# 2.net
KiCad netlist of a schematic drawn in EAGLE
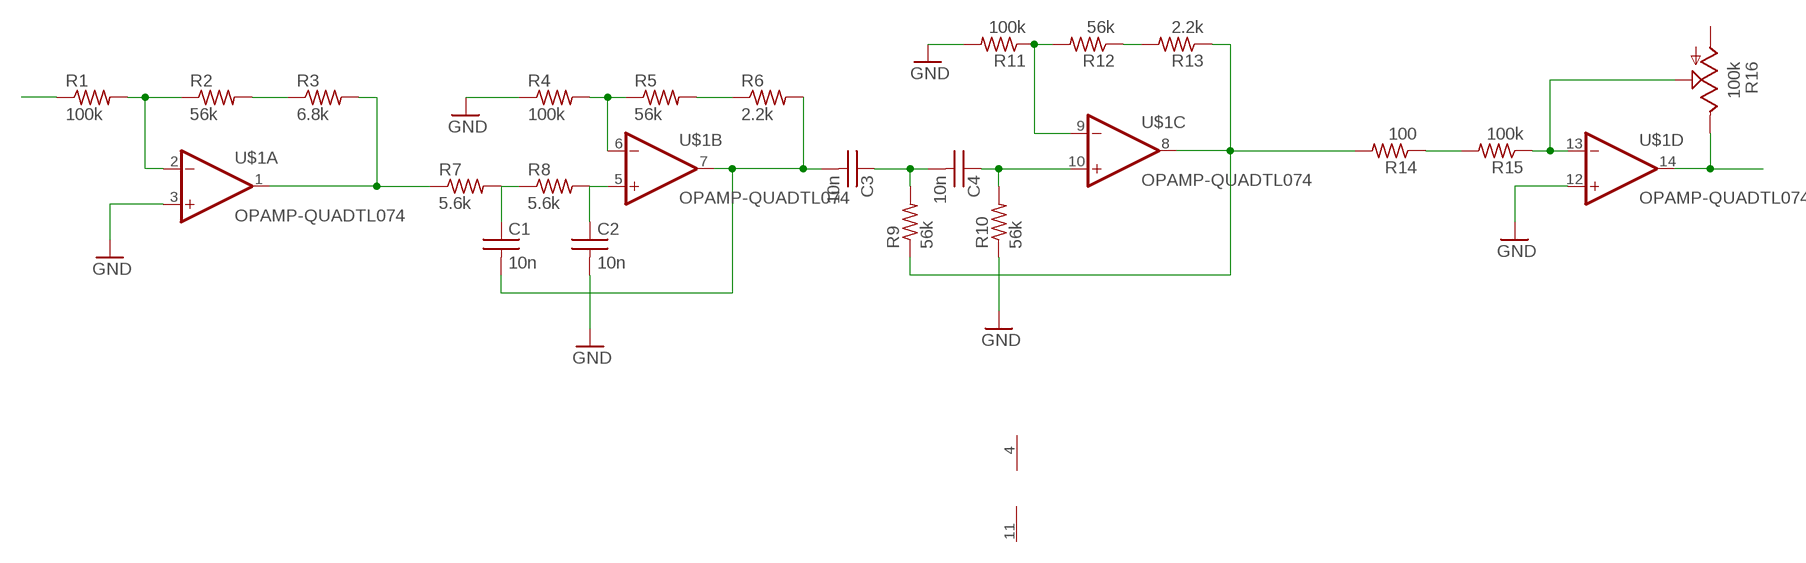
[diagram p0: schematic, sheet 1]

(export (version "E")
  (design (tool "Eeschema 10.0.6"))
  (components
    (comp (ref "C1")
      (value "10n")
      (footprint "eagle-import:BOX-2.5MM-7.2MM")
      (libsource (lib "eagle-import") (part "CAPACITOR"))
    )
    (comp (ref "C2")
      (value "10n")
      (footprint "eagle-import:BOX-2.5MM-7.2MM")
      (libsource (lib "eagle-import") (part "CAPACITOR"))
    )
    (comp (ref "C3")
      (value "10n")
      (footprint "eagle-import:BOX-2.5MM-7.2MM")
      (libsource (lib "eagle-import") (part "CAPACITOR"))
    )
    (comp (ref "C4")
      (value "10n")
      (footprint "eagle-import:BOX-2.5MM-7.2MM")
      (libsource (lib "eagle-import") (part "CAPACITOR"))
    )
    (comp (ref "R1")
      (value "100k")
      (footprint "eagle-import:0.25W-0.4IN-CARBONFILM")
      (libsource (lib "eagle-import") (part "RESISTOR0.25W-0.4IN-CARBONFILM"))
    )
    (comp (ref "R2")
      (value "56k")
      (footprint "eagle-import:0.25W-0.4IN-CARBONFILM")
      (libsource (lib "eagle-import") (part "RESISTOR0.25W-0.4IN-CARBONFILM"))
    )
    (comp (ref "R3")
      (value "6.8k")
      (footprint "eagle-import:0.25W-0.4IN-CARBONFILM")
      (libsource (lib "eagle-import") (part "RESISTOR0.25W-0.4IN-CARBONFILM"))
    )
    (comp (ref "R4")
      (value "100k")
      (footprint "eagle-import:0.25W-0.4IN-CARBONFILM")
      (libsource (lib "eagle-import") (part "RESISTOR0.25W-0.4IN-CARBONFILM"))
    )
    (comp (ref "R5")
      (value "56k")
      (footprint "eagle-import:0.25W-0.4IN-CARBONFILM")
      (libsource (lib "eagle-import") (part "RESISTOR0.25W-0.4IN-CARBONFILM"))
    )
    (comp (ref "R6")
      (value "2.2k")
      (footprint "eagle-import:0.25W-0.4IN-CARBONFILM")
      (libsource (lib "eagle-import") (part "RESISTOR0.25W-0.4IN-CARBONFILM"))
    )
    (comp (ref "R7")
      (value "5.6k")
      (footprint "eagle-import:0.25W-0.4IN-CARBONFILM")
      (libsource (lib "eagle-import") (part "RESISTOR0.25W-0.4IN-CARBONFILM"))
    )
    (comp (ref "R8")
      (value "5.6k")
      (footprint "eagle-import:0.25W-0.4IN-CARBONFILM")
      (libsource (lib "eagle-import") (part "RESISTOR0.25W-0.4IN-CARBONFILM"))
    )
    (comp (ref "R9")
      (value "56k")
      (footprint "eagle-import:0.25W-0.4IN-CARBONFILM")
      (libsource (lib "eagle-import") (part "RESISTOR0.25W-0.4IN-CARBONFILM"))
    )
    (comp (ref "R10")
      (value "56k")
      (footprint "eagle-import:0.25W-0.4IN-CARBONFILM")
      (libsource (lib "eagle-import") (part "RESISTOR0.25W-0.4IN-CARBONFILM"))
    )
    (comp (ref "R11")
      (value "100k")
      (footprint "eagle-import:0.25W-0.4IN-CARBONFILM")
      (libsource (lib "eagle-import") (part "RESISTOR0.25W-0.4IN-CARBONFILM"))
    )
    (comp (ref "R12")
      (value "56k")
      (footprint "eagle-import:0.25W-0.4IN-CARBONFILM")
      (libsource (lib "eagle-import") (part "RESISTOR0.25W-0.4IN-CARBONFILM"))
    )
    (comp (ref "R13")
      (value "2.2k")
      (footprint "eagle-import:0.25W-0.4IN-CARBONFILM")
      (libsource (lib "eagle-import") (part "RESISTOR0.25W-0.4IN-CARBONFILM"))
    )
    (comp (ref "R14")
      (value "100")
      (footprint "eagle-import:0.25W-0.4IN-CARBONFILM")
      (libsource (lib "eagle-import") (part "RESISTOR0.25W-0.4IN-CARBONFILM"))
    )
    (comp (ref "R15")
      (value "100k")
      (footprint "eagle-import:0.25W-0.4IN-CARBONFILM")
      (libsource (lib "eagle-import") (part "RESISTOR0.25W-0.4IN-CARBONFILM"))
    )
    (comp (ref "R16")
      (value "100k")
      (footprint "eagle-import:POT-SIDE-16MM-BITECH-P160KN")
      (libsource (lib "eagle-import") (part "POTENTIOMETERHORIZONTAL"))
    )
    (comp (ref "U$1")
      (value "OPAMP-QUADTL074")
      (footprint "eagle-import:DIP14")
      (libsource (lib "eagle-import") (part "OPAMP-QUADTL074"))
    )
  )
  (nets
    (net (code "1") (name "/VCC") (class "Default")
      (node (ref "U$1") (pin "4") (pinfunction "VCC_4") (pintype "power_in"))
    )
    (net (code "2") (name "/VEE") (class "Default")
      (node (ref "U$1") (pin "11") (pinfunction "VEE_11") (pintype "power_in"))
    )
    (net (code "3") (name "0") (class "Default")
      (node (ref "C2") (pin "P$2") (pinfunction "2_P$2") (pintype "passive"))
      (node (ref "R10") (pin "1") (pinfunction "1_1") (pintype "passive"))
      (node (ref "R11") (pin "2") (pinfunction "2_2") (pintype "passive"))
      (node (ref "R4") (pin "1") (pinfunction "1_1") (pintype "passive"))
      (node (ref "U$1") (pin "12") (pinfunction "IN+_12") (pintype "input"))
      (node (ref "U$1") (pin "3") (pinfunction "IN+_3") (pintype "input"))
    )
    (net (code "4") (name "Net-(C1-1)") (class "Default")
      (node (ref "C1") (pin "P$1") (pinfunction "1_P$1") (pintype "passive"))
      (node (ref "R7") (pin "2") (pinfunction "2_2") (pintype "passive"))
      (node (ref "R8") (pin "1") (pinfunction "1_1") (pintype "passive"))
    )
    (net (code "5") (name "Net-(C1-2)") (class "Default")
      (node (ref "C1") (pin "P$2") (pinfunction "2_P$2") (pintype "passive"))
      (node (ref "C3") (pin "P$2") (pinfunction "2_P$2") (pintype "passive"))
      (node (ref "R6") (pin "2") (pinfunction "2_2") (pintype "passive"))
      (node (ref "U$1") (pin "7") (pinfunction "OUT_7") (pintype "output"))
    )
    (net (code "6") (name "Net-(C2-1)") (class "Default")
      (node (ref "C2") (pin "P$1") (pinfunction "1_P$1") (pintype "passive"))
      (node (ref "R8") (pin "2") (pinfunction "2_2") (pintype "passive"))
      (node (ref "U$1") (pin "5") (pinfunction "IN+_5") (pintype "input"))
    )
    (net (code "7") (name "Net-(C3-1)") (class "Default")
      (node (ref "C3") (pin "P$1") (pinfunction "1_P$1") (pintype "passive"))
      (node (ref "C4") (pin "P$2") (pinfunction "2_P$2") (pintype "passive"))
      (node (ref "R9") (pin "2") (pinfunction "2_2") (pintype "passive"))
    )
    (net (code "8") (name "Net-(C4-1)") (class "Default")
      (node (ref "C4") (pin "P$1") (pinfunction "1_P$1") (pintype "passive"))
      (node (ref "R10") (pin "2") (pinfunction "2_2") (pintype "passive"))
      (node (ref "U$1") (pin "10") (pinfunction "IN+_10") (pintype "input"))
    )
    (net (code "9") (name "Net-(R2-Pad2)") (class "Default")
      (node (ref "R2") (pin "2") (pinfunction "2_2") (pintype "passive"))
      (node (ref "R3") (pin "1") (pinfunction "1_1") (pintype "passive"))
    )
    (net (code "10") (name "Net-(R5-Pad2)") (class "Default")
      (node (ref "R5") (pin "2") (pinfunction "2_2") (pintype "passive"))
      (node (ref "R6") (pin "1") (pinfunction "1_1") (pintype "passive"))
    )
    (net (code "11") (name "Net-(R12-Pad1)") (class "Default")
      (node (ref "R12") (pin "1") (pinfunction "1_1") (pintype "passive"))
      (node (ref "R13") (pin "2") (pinfunction "2_2") (pintype "passive"))
    )
    (net (code "12") (name "Net-(R14-Pad1)") (class "Default")
      (node (ref "R14") (pin "1") (pinfunction "1_1") (pintype "passive"))
      (node (ref "R15") (pin "2") (pinfunction "2_2") (pintype "passive"))
    )
    (net (code "13") (name "Net-(R16-2)") (class "Default")
      (node (ref "R15") (pin "1") (pinfunction "1_1") (pintype "passive"))
      (node (ref "R16") (pin "P$2") (pinfunction "2_P$2") (pintype "passive"))
      (node (ref "U$1") (pin "13") (pinfunction "IN-_13") (pintype "input"))
    )
    (net (code "14") (name "Net-(R16-3)") (class "Default")
      (node (ref "R16") (pin "P$3") (pinfunction "3_P$3") (pintype "passive"))
      (node (ref "U$1") (pin "14") (pinfunction "OUT_14") (pintype "output"))
    )
    (net (code "15") (name "Net-(U$1A-IN-)") (class "Default")
      (node (ref "R1") (pin "2") (pinfunction "2_2") (pintype "passive"))
      (node (ref "R2") (pin "1") (pinfunction "1_1") (pintype "passive"))
      (node (ref "U$1") (pin "2") (pinfunction "IN-_2") (pintype "input"))
    )
    (net (code "16") (name "Net-(U$1A-OUT)") (class "Default")
      (node (ref "R3") (pin "2") (pinfunction "2_2") (pintype "passive"))
      (node (ref "R7") (pin "1") (pinfunction "1_1") (pintype "passive"))
      (node (ref "U$1") (pin "1") (pinfunction "OUT_1") (pintype "output"))
    )
    (net (code "17") (name "Net-(U$1B-IN-)") (class "Default")
      (node (ref "R4") (pin "2") (pinfunction "2_2") (pintype "passive"))
      (node (ref "R5") (pin "1") (pinfunction "1_1") (pintype "passive"))
      (node (ref "U$1") (pin "6") (pinfunction "IN-_6") (pintype "input"))
    )
    (net (code "18") (name "Net-(U$1C-IN-)") (class "Default")
      (node (ref "R11") (pin "1") (pinfunction "1_1") (pintype "passive"))
      (node (ref "R12") (pin "2") (pinfunction "2_2") (pintype "passive"))
      (node (ref "U$1") (pin "9") (pinfunction "IN-_9") (pintype "input"))
    )
    (net (code "19") (name "Net-(U$1C-OUT)") (class "Default")
      (node (ref "R13") (pin "1") (pinfunction "1_1") (pintype "passive"))
      (node (ref "R14") (pin "2") (pinfunction "2_2") (pintype "passive"))
      (node (ref "R9") (pin "1") (pinfunction "1_1") (pintype "passive"))
      (node (ref "U$1") (pin "8") (pinfunction "OUT_8") (pintype "output"))
    )
    (net (code "20") (name "unconnected-(R1-Pad1)") (class "Default")
      (node (ref "R1") (pin "1") (pinfunction "1_1") (pintype "passive"))
    )
    (net (code "21") (name "unconnected-(R16-1-PadP$1)") (class "Default")
      (node (ref "R16") (pin "P$1") (pinfunction "1_P$1") (pintype "passive"))
    )
  )
)
